# AGC_NEW.net
KiCad netlist of a schematic drawn in Altium Designer
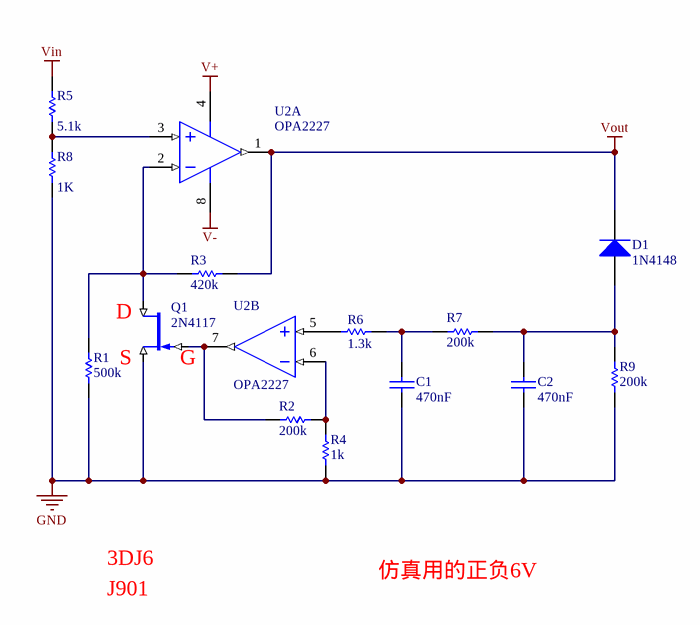
[diagram p0: AGC电路NEW.SchDoc]

(export (version "E")
  (design (tool "Eeschema 10.0.6"))
  (components
    (comp (ref "C1")
      (value "470nF")
      (footprint "0805CAP")
      (description "Capacitor")
      (fields (field (name "PUBLISHER") "Altium Limited"))
      (libsource (lib "Miscellaneous Devices") (part "Cap"))
    )
    (comp (ref "C2")
      (value "470nF")
      (footprint "0805CAP")
      (description "Capacitor")
      (fields (field (name "PUBLISHER") "Altium Limited"))
      (libsource (lib "Miscellaneous Devices") (part "Cap"))
    )
    (comp (ref "D1")
      (value "1N4148")
      (footprint "SMC")
      (description "1 Amp General Purpose Rectifier")
      (fields (field (name "PUBLISHER") "Altium Limited"))
      (libsource (lib "Miscellaneous Devices") (part "Diode 1N4001"))
    )
    (comp (ref "Q1")
      (value "2N4117")
      (description "N-Channel JFET")
      (libsource (lib "场效应管及可控硅") (part "2N4117"))
    )
    (comp (ref "R1")
      (value "500k")
      (footprint "0805")
      (description "Resistor")
      (fields (field (name "PUBLISHER") "Altium Limited"))
      (libsource (lib "Miscellaneous Devices") (part "Res1"))
    )
    (comp (ref "R2")
      (value "200k")
      (footprint "0805")
      (description "Resistor")
      (fields (field (name "PUBLISHER") "Altium Limited"))
      (libsource (lib "Miscellaneous Devices") (part "Res1"))
    )
    (comp (ref "R3")
      (value "420k")
      (footprint "0805")
      (description "Resistor")
      (fields (field (name "PUBLISHER") "Altium Limited"))
      (libsource (lib "Miscellaneous Devices") (part "Res1"))
    )
    (comp (ref "R4")
      (value "1k")
      (footprint "0805")
      (description "Resistor")
      (fields (field (name "PUBLISHER") "Altium Limited"))
      (libsource (lib "Miscellaneous Devices") (part "Res1"))
    )
    (comp (ref "R5")
      (value "5.1k")
      (footprint "0805")
      (description "Resistor")
      (fields (field (name "PUBLISHER") "Altium Limited"))
      (libsource (lib "Miscellaneous Devices") (part "Res1"))
    )
    (comp (ref "R6")
      (value "1.3k")
      (footprint "0805")
      (description "Resistor")
      (fields (field (name "PUBLISHER") "Altium Limited"))
      (libsource (lib "Miscellaneous Devices") (part "Res1"))
    )
    (comp (ref "R7")
      (value "200k")
      (footprint "0805")
      (description "Resistor")
      (fields (field (name "PUBLISHER") "Altium Limited"))
      (libsource (lib "Miscellaneous Devices") (part "Res1"))
    )
    (comp (ref "R8")
      (value "1K")
      (footprint "0805")
      (description "Resistor")
      (fields (field (name "PUBLISHER") "Altium Limited"))
      (libsource (lib "Miscellaneous Devices") (part "Res1"))
    )
    (comp (ref "R9")
      (value "200k")
      (footprint "0805")
      (description "Resistor")
      (fields (field (name "PUBLISHER") "Altium Limited"))
      (libsource (lib "Miscellaneous Devices") (part "Res1"))
    )
    (comp (ref "U2") (value "OPA2227") (footprint "SO-8") (libsource (lib "MB784") (part "OPA2379AID")))
  )
  (nets
    (net (code "1") (name "GND") (class "Default")
      (node (ref "C1") (pin "1") (pinfunction "1_1") (pintype "passive"))
      (node (ref "C2") (pin "1") (pinfunction "1_1") (pintype "passive"))
      (node (ref "Q1") (pin "3") (pinfunction "S_3") (pintype "input"))
      (node (ref "R1") (pin "1") (pinfunction "1_1") (pintype "passive"))
      (node (ref "R4") (pin "1") (pinfunction "1_1") (pintype "passive"))
      (node (ref "R8") (pin "1") (pinfunction "1_1") (pintype "passive"))
      (node (ref "R9") (pin "1") (pinfunction "1_1") (pintype "passive"))
    )
    (net (code "2") (name "Net-(C1-Pad2)") (class "Default")
      (node (ref "C1") (pin "2") (pinfunction "2_2") (pintype "passive"))
      (node (ref "R6") (pin "2") (pinfunction "2_2") (pintype "passive"))
      (node (ref "R7") (pin "1") (pinfunction "1_1") (pintype "passive"))
    )
    (net (code "3") (name "Net-(D1-A)") (class "Default")
      (node (ref "C2") (pin "2") (pinfunction "2_2") (pintype "passive"))
      (node (ref "D1") (pin "1") (pinfunction "A_1") (pintype "passive"))
      (node (ref "R7") (pin "2") (pinfunction "2_2") (pintype "passive"))
      (node (ref "R9") (pin "2") (pinfunction "2_2") (pintype "passive"))
    )
    (net (code "4") (name "Net-(Q1-D)") (class "Default")
      (node (ref "Q1") (pin "1") (pinfunction "D_1") (pintype "input"))
      (node (ref "R1") (pin "2") (pinfunction "2_2") (pintype "passive"))
      (node (ref "R3") (pin "2") (pinfunction "2_2") (pintype "passive"))
      (node (ref "U2") (pin "2") (pinfunction "IN-A_2") (pintype "input"))
    )
    (net (code "5") (name "Net-(Q1-G)") (class "Default")
      (node (ref "Q1") (pin "2") (pinfunction "G_2") (pintype "input"))
      (node (ref "R2") (pin "2") (pinfunction "2_2") (pintype "passive"))
      (node (ref "U2") (pin "7") (pinfunction "OUTB_7") (pintype "output"))
    )
    (net (code "6") (name "Net-(U2A-IN+A)") (class "Default")
      (node (ref "R5") (pin "2") (pinfunction "2_2") (pintype "passive"))
      (node (ref "R8") (pin "2") (pinfunction "2_2") (pintype "passive"))
      (node (ref "U2") (pin "3") (pinfunction "IN+A_3") (pintype "input"))
    )
    (net (code "7") (name "Net-(U2B-IN+B)") (class "Default")
      (node (ref "R6") (pin "1") (pinfunction "1_1") (pintype "passive"))
      (node (ref "U2") (pin "5") (pinfunction "IN+B_5") (pintype "input"))
    )
    (net (code "8") (name "Net-(U2B-IN-B)") (class "Default")
      (node (ref "R2") (pin "1") (pinfunction "1_1") (pintype "passive"))
      (node (ref "R4") (pin "2") (pinfunction "2_2") (pintype "passive"))
      (node (ref "U2") (pin "6") (pinfunction "IN-B_6") (pintype "input"))
    )
    (net (code "9") (name "V+") (class "Default")
      (node (ref "U2") (pin "4") (pinfunction "V-_4") (pintype "power_in"))
    )
    (net (code "10") (name "V-") (class "Default")
      (node (ref "U2") (pin "8") (pinfunction "V+_8") (pintype "power_in"))
    )
    (net (code "11") (name "Vin") (class "Default")
      (node (ref "R5") (pin "1") (pinfunction "1_1") (pintype "passive"))
    )
    (net (code "12") (name "Vout") (class "Default")
      (node (ref "D1") (pin "2") (pinfunction "K_2") (pintype "passive"))
      (node (ref "R3") (pin "1") (pinfunction "1_1") (pintype "passive"))
      (node (ref "U2") (pin "1") (pinfunction "OUTA_1") (pintype "output"))
    )
  )
)
